# TutorialPCB.net
KiCad netlist of a schematic drawn in EAGLE
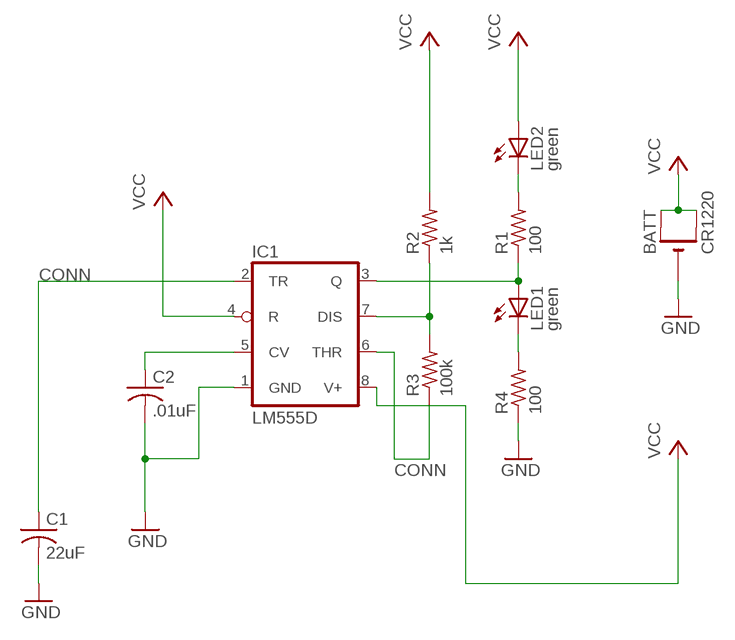
[diagram p0: schematic, sheet 1]

(export (version "E")
  (design (tool "Eeschema 10.0.6"))
  (components
    (comp (ref "BATT")
      (value "CR1220")
      (footprint "eagle-import:CR1220-SMD")
      (libsource (lib "eagle-import") (part "CR1220SMT"))
    )
    (comp (ref "C1")
      (value "22uF")
      (footprint "eagle-import:C0805")
      (libsource (lib "eagle-import") (part "C-USC0805"))
    )
    (comp (ref "C2")
      (value ".01uF")
      (footprint "eagle-import:C0805")
      (libsource (lib "eagle-import") (part "C-USC0805"))
    )
    (comp (ref "IC1")
      (value "LM555D")
      (footprint "eagle-import:SO08")
      (libsource (lib "eagle-import") (part "555DLM"))
    )
    (comp (ref "LED1")
      (value "green")
      (footprint "eagle-import:CHIPLED_0805")
      (libsource (lib "eagle-import") (part "LEDCHIPLED_0805"))
    )
    (comp (ref "LED2")
      (value "green")
      (footprint "eagle-import:CHIPLED_0805")
      (libsource (lib "eagle-import") (part "LEDCHIPLED_0805"))
    )
    (comp (ref "R1")
      (value "100")
      (footprint "eagle-import:R0805")
      (libsource (lib "eagle-import") (part "R-US_R0805"))
    )
    (comp (ref "R2")
      (value "1k")
      (footprint "eagle-import:R0805")
      (libsource (lib "eagle-import") (part "R-US_R0805"))
    )
    (comp (ref "R3")
      (value "100k")
      (footprint "eagle-import:R0805")
      (libsource (lib "eagle-import") (part "R-US_R0805"))
    )
    (comp (ref "R4")
      (value "100")
      (footprint "eagle-import:R0805")
      (libsource (lib "eagle-import") (part "R-US_R0805"))
    )
  )
  (nets
    (net (code "1") (name "/CONN") (class "Default")
      (node (ref "C1") (pin "1") (pinfunction "1_1") (pintype "passive"))
      (node (ref "IC1") (pin "2") (pinfunction "TR_2") (pintype "input"))
      (node (ref "IC1") (pin "6") (pinfunction "THR_6") (pintype "input"))
      (node (ref "R3") (pin "1") (pinfunction "1_1") (pintype "passive"))
    )
    (net (code "2") (name "GND") (class "Default")
      (node (ref "BATT") (pin "-") (pinfunction "-_-") (pintype "passive"))
      (node (ref "C1") (pin "2") (pinfunction "2_2") (pintype "passive"))
      (node (ref "C2") (pin "2") (pinfunction "2_2") (pintype "passive"))
      (node (ref "IC1") (pin "1") (pinfunction "GND_1") (pintype "power_in"))
      (node (ref "R4") (pin "1") (pinfunction "1_1") (pintype "passive"))
    )
    (net (code "3") (name "Net-(IC1-CV)") (class "Default")
      (node (ref "C2") (pin "1") (pinfunction "1_1") (pintype "passive"))
      (node (ref "IC1") (pin "5") (pinfunction "CV_5") (pintype "input"))
    )
    (net (code "4") (name "Net-(IC1-DIS)") (class "Default")
      (node (ref "IC1") (pin "7") (pinfunction "DIS_7") (pintype "input"))
      (node (ref "R2") (pin "1") (pinfunction "1_1") (pintype "passive"))
      (node (ref "R3") (pin "2") (pinfunction "2_2") (pintype "passive"))
    )
    (net (code "5") (name "Net-(IC1-Q)") (class "Default")
      (node (ref "IC1") (pin "3") (pinfunction "Q_3") (pintype "output"))
      (node (ref "LED1") (pin "A") (pinfunction "A_A") (pintype "passive"))
      (node (ref "R1") (pin "1") (pinfunction "1_1") (pintype "passive"))
    )
    (net (code "6") (name "Net-(LED1-PadC)") (class "Default")
      (node (ref "LED1") (pin "C") (pinfunction "C_C") (pintype "passive"))
      (node (ref "R4") (pin "2") (pinfunction "2_2") (pintype "passive"))
    )
    (net (code "7") (name "Net-(LED2-PadC)") (class "Default")
      (node (ref "LED2") (pin "C") (pinfunction "C_C") (pintype "passive"))
      (node (ref "R1") (pin "2") (pinfunction "2_2") (pintype "passive"))
    )
    (net (code "8") (name "VCC") (class "Default")
      (node (ref "BATT") (pin "+$1") (pinfunction "+_+$1") (pintype "passive"))
      (node (ref "BATT") (pin "+$2") (pinfunction "+1_+$2") (pintype "passive"))
      (node (ref "IC1") (pin "4") (pinfunction "R_4") (pintype "input"))
      (node (ref "IC1") (pin "8") (pinfunction "V+_8") (pintype "power_in"))
      (node (ref "LED2") (pin "A") (pinfunction "A_A") (pintype "passive"))
      (node (ref "R2") (pin "2") (pinfunction "2_2") (pintype "passive"))
    )
  )
)
